# led_2835_rectangle_49point9X2point6cm.net
KiCad netlist of a schematic drawn in Altium Designer
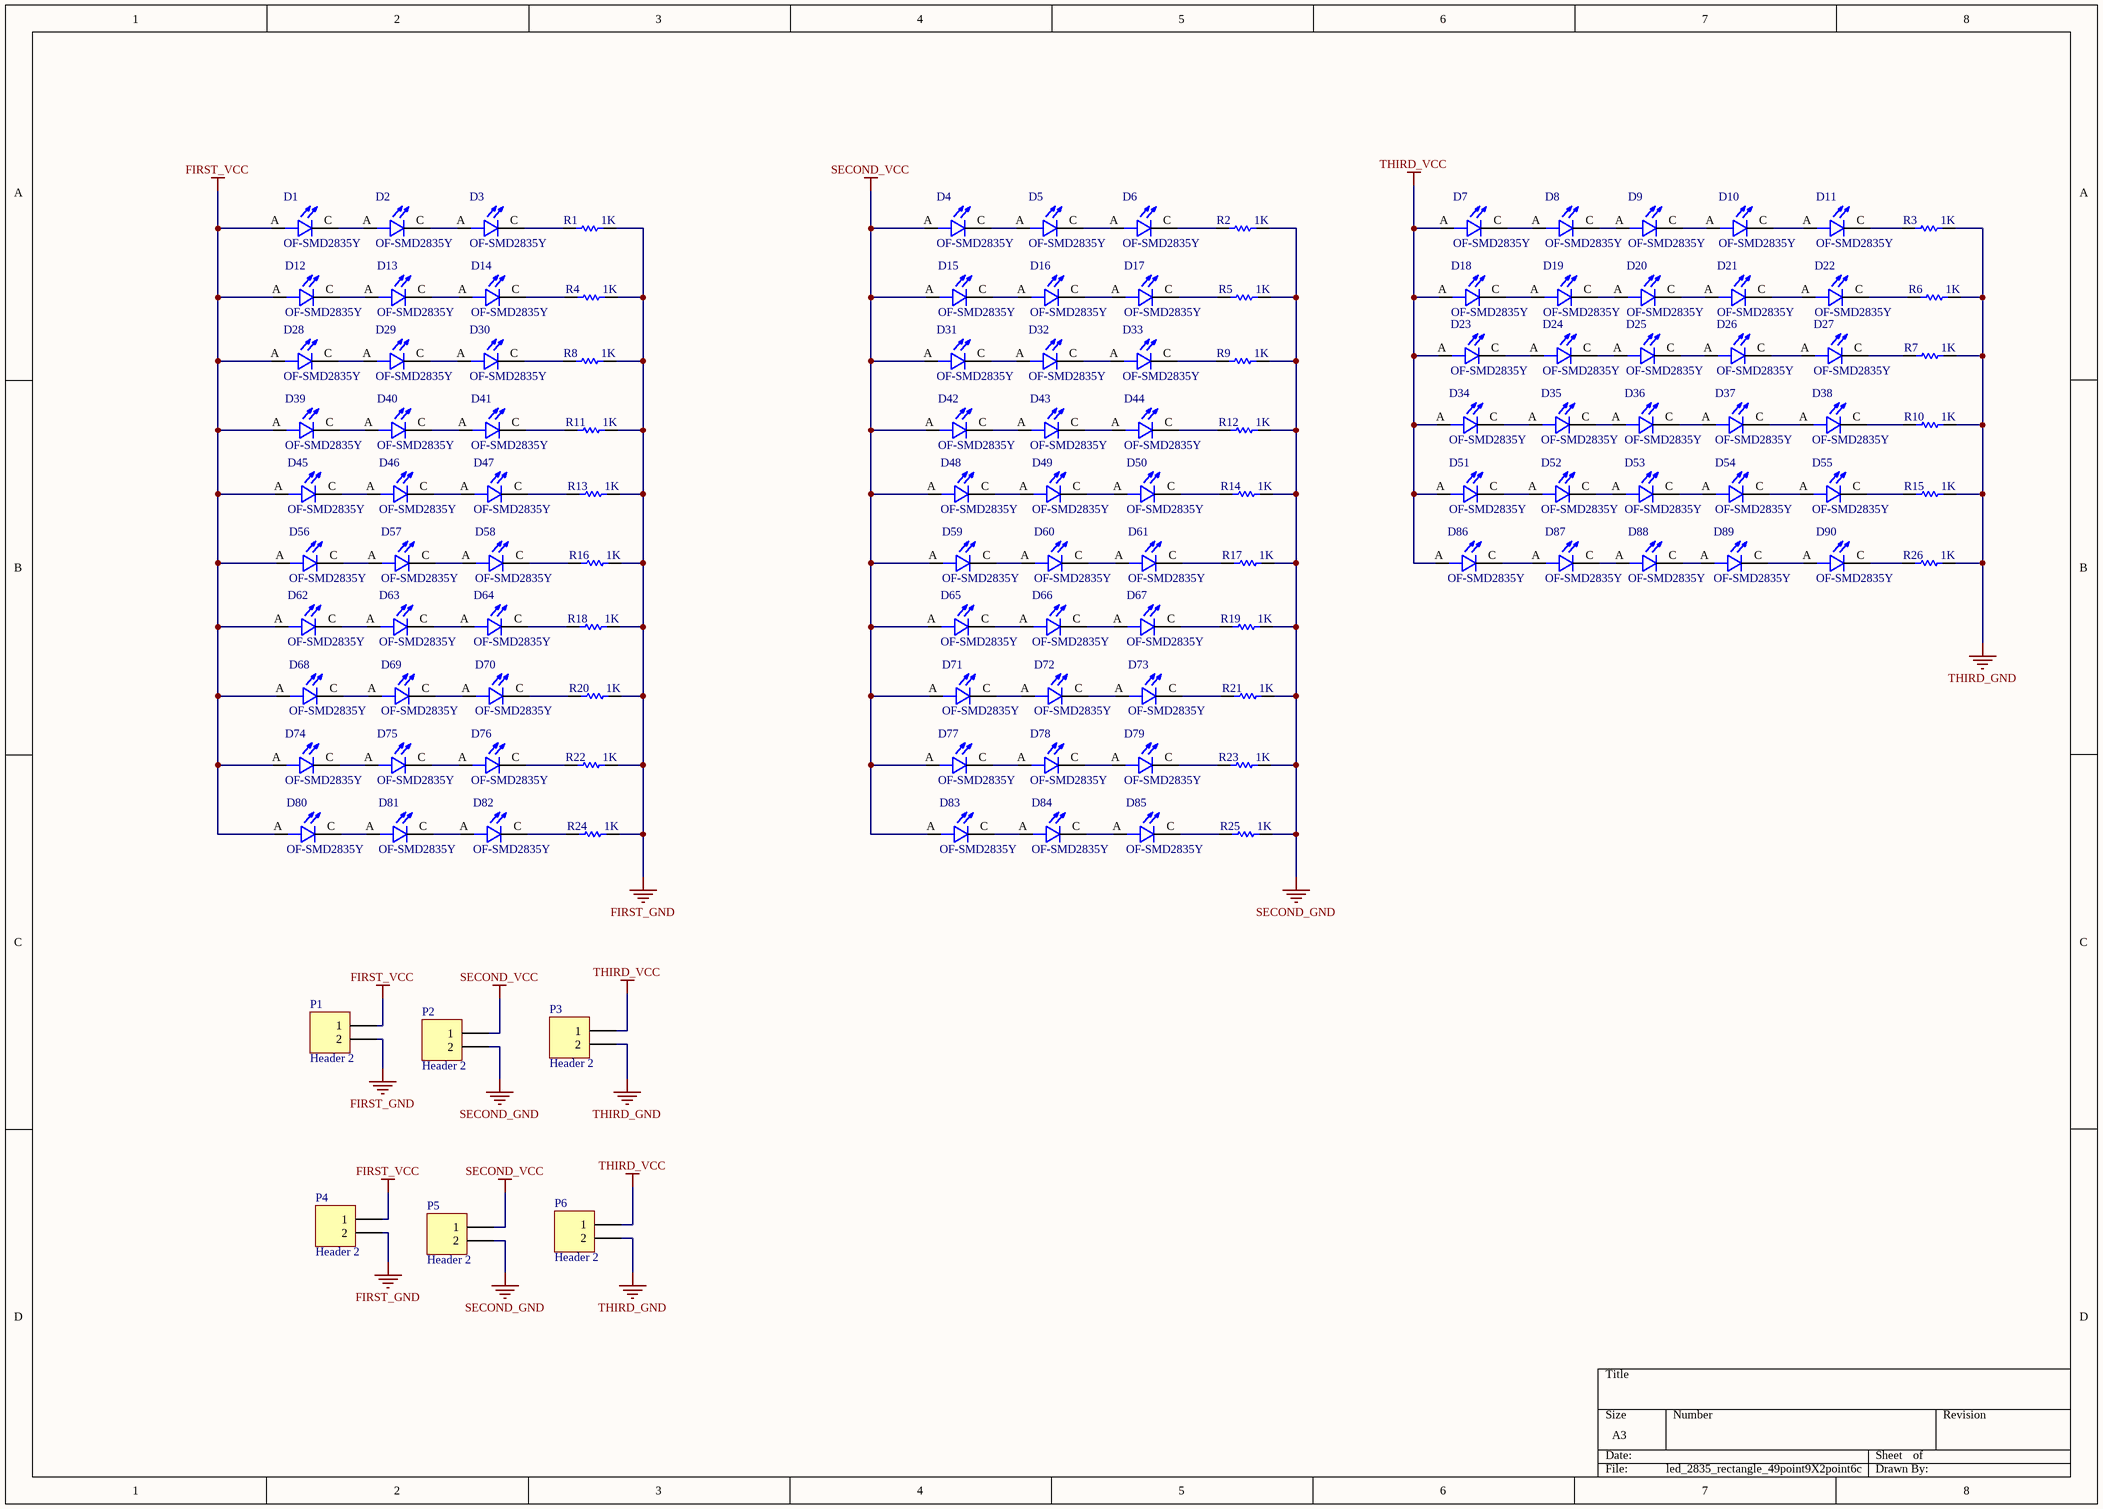
[diagram p0: led_2835_rectangle_49point9X2point6cm.SchDoc]

(export (version "E")
  (design (tool "Eeschema 10.0.6"))
  (components
    (comp (ref "D1")
      (value "OF-SMD2835Y")
      (footprint "LED_OF-SMD2835Y")
      (description "LED; SMD; 2835, PLCC2; yellow; 2200-2800mcd; 2.8x3.5x0.75mm; 120Â°")
      (libsource (lib "") (part "OF-SMD2835Y_4"))
    )
    (comp (ref "D2")
      (value "OF-SMD2835Y")
      (footprint "LED_OF-SMD2835Y")
      (description "LED; SMD; 2835, PLCC2; yellow; 2200-2800mcd; 2.8x3.5x0.75mm; 120Â°")
      (libsource (lib "") (part "OF-SMD2835Y_4"))
    )
    (comp (ref "D3")
      (value "OF-SMD2835Y")
      (footprint "LED_OF-SMD2835Y")
      (description "LED; SMD; 2835, PLCC2; yellow; 2200-2800mcd; 2.8x3.5x0.75mm; 120Â°")
      (libsource (lib "") (part "OF-SMD2835Y_4"))
    )
    (comp (ref "D4")
      (value "OF-SMD2835Y")
      (footprint "LED_OF-SMD2835Y")
      (description "LED; SMD; 2835, PLCC2; yellow; 2200-2800mcd; 2.8x3.5x0.75mm; 120Â°")
      (libsource (lib "") (part "OF-SMD2835Y_4"))
    )
    (comp (ref "D5")
      (value "OF-SMD2835Y")
      (footprint "LED_OF-SMD2835Y")
      (description "LED; SMD; 2835, PLCC2; yellow; 2200-2800mcd; 2.8x3.5x0.75mm; 120Â°")
      (libsource (lib "") (part "OF-SMD2835Y_4"))
    )
    (comp (ref "D6")
      (value "OF-SMD2835Y")
      (footprint "LED_OF-SMD2835Y")
      (description "LED; SMD; 2835, PLCC2; yellow; 2200-2800mcd; 2.8x3.5x0.75mm; 120Â°")
      (libsource (lib "") (part "OF-SMD2835Y_4"))
    )
    (comp (ref "D7")
      (value "OF-SMD2835Y")
      (footprint "LED_OF-SMD2835Y")
      (description "LED; SMD; 2835, PLCC2; yellow; 2200-2800mcd; 2.8x3.5x0.75mm; 120Â°")
      (libsource (lib "") (part "OF-SMD2835Y_3"))
    )
    (comp (ref "D8")
      (value "OF-SMD2835Y")
      (footprint "LED_OF-SMD2835Y")
      (description "LED; SMD; 2835, PLCC2; yellow; 2200-2800mcd; 2.8x3.5x0.75mm; 120Â°")
      (libsource (lib "") (part "OF-SMD2835Y_3"))
    )
    (comp (ref "D9")
      (value "OF-SMD2835Y")
      (footprint "LED_OF-SMD2835Y")
      (description "LED; SMD; 2835, PLCC2; yellow; 2200-2800mcd; 2.8x3.5x0.75mm; 120Â°")
      (libsource (lib "") (part "OF-SMD2835Y_3"))
    )
    (comp (ref "D10")
      (value "OF-SMD2835Y")
      (footprint "LED_OF-SMD2835Y")
      (description "LED; SMD; 2835, PLCC2; yellow; 2200-2800mcd; 2.8x3.5x0.75mm; 120Â°")
      (libsource (lib "") (part "OF-SMD2835Y_3"))
    )
    (comp (ref "D11")
      (value "OF-SMD2835Y")
      (footprint "LED_OF-SMD2835Y")
      (description "LED; SMD; 2835, PLCC2; yellow; 2200-2800mcd; 2.8x3.5x0.75mm; 120Â°")
      (libsource (lib "") (part "OF-SMD2835Y_3"))
    )
    (comp (ref "D12")
      (value "OF-SMD2835Y")
      (footprint "LED_OF-SMD2835Y")
      (description "LED; SMD; 2835, PLCC2; yellow; 2200-2800mcd; 2.8x3.5x0.75mm; 120Â°")
      (libsource (lib "") (part "OF-SMD2835Y_1"))
    )
    (comp (ref "D13")
      (value "OF-SMD2835Y")
      (footprint "LED_OF-SMD2835Y")
      (description "LED; SMD; 2835, PLCC2; yellow; 2200-2800mcd; 2.8x3.5x0.75mm; 120Â°")
      (libsource (lib "") (part "OF-SMD2835Y_1"))
    )
    (comp (ref "D14")
      (value "OF-SMD2835Y")
      (footprint "LED_OF-SMD2835Y")
      (description "LED; SMD; 2835, PLCC2; yellow; 2200-2800mcd; 2.8x3.5x0.75mm; 120Â°")
      (libsource (lib "") (part "OF-SMD2835Y_1"))
    )
    (comp (ref "D15")
      (value "OF-SMD2835Y")
      (footprint "LED_OF-SMD2835Y")
      (description "LED; SMD; 2835, PLCC2; yellow; 2200-2800mcd; 2.8x3.5x0.75mm; 120Â°")
      (libsource (lib "") (part "OF-SMD2835Y_3"))
    )
    (comp (ref "D16")
      (value "OF-SMD2835Y")
      (footprint "LED_OF-SMD2835Y")
      (description "LED; SMD; 2835, PLCC2; yellow; 2200-2800mcd; 2.8x3.5x0.75mm; 120Â°")
      (libsource (lib "") (part "OF-SMD2835Y_3"))
    )
    (comp (ref "D17")
      (value "OF-SMD2835Y")
      (footprint "LED_OF-SMD2835Y")
      (description "LED; SMD; 2835, PLCC2; yellow; 2200-2800mcd; 2.8x3.5x0.75mm; 120Â°")
      (libsource (lib "") (part "OF-SMD2835Y_3"))
    )
    (comp (ref "D18")
      (value "OF-SMD2835Y")
      (footprint "LED_OF-SMD2835Y")
      (description "LED; SMD; 2835, PLCC2; yellow; 2200-2800mcd; 2.8x3.5x0.75mm; 120Â°")
      (libsource (lib "") (part "OF-SMD2835Y_3"))
    )
    (comp (ref "D19")
      (value "OF-SMD2835Y")
      (footprint "LED_OF-SMD2835Y")
      (description "LED; SMD; 2835, PLCC2; yellow; 2200-2800mcd; 2.8x3.5x0.75mm; 120Â°")
      (libsource (lib "") (part "OF-SMD2835Y_3"))
    )
    (comp (ref "D20")
      (value "OF-SMD2835Y")
      (footprint "LED_OF-SMD2835Y")
      (description "LED; SMD; 2835, PLCC2; yellow; 2200-2800mcd; 2.8x3.5x0.75mm; 120Â°")
      (libsource (lib "") (part "OF-SMD2835Y_3"))
    )
    (comp (ref "D21")
      (value "OF-SMD2835Y")
      (footprint "LED_OF-SMD2835Y")
      (description "LED; SMD; 2835, PLCC2; yellow; 2200-2800mcd; 2.8x3.5x0.75mm; 120Â°")
      (libsource (lib "") (part "OF-SMD2835Y_3"))
    )
    (comp (ref "D22")
      (value "OF-SMD2835Y")
      (footprint "LED_OF-SMD2835Y")
      (description "LED; SMD; 2835, PLCC2; yellow; 2200-2800mcd; 2.8x3.5x0.75mm; 120Â°")
      (libsource (lib "") (part "OF-SMD2835Y_3"))
    )
    (comp (ref "D23")
      (value "OF-SMD2835Y")
      (footprint "LED_OF-SMD2835Y")
      (description "LED; SMD; 2835, PLCC2; yellow; 2200-2800mcd; 2.8x3.5x0.75mm; 120Â°")
      (libsource (lib "") (part "OF-SMD2835Y_3"))
    )
    (comp (ref "D24")
      (value "OF-SMD2835Y")
      (footprint "LED_OF-SMD2835Y")
      (description "LED; SMD; 2835, PLCC2; yellow; 2200-2800mcd; 2.8x3.5x0.75mm; 120Â°")
      (libsource (lib "") (part "OF-SMD2835Y_3"))
    )
    (comp (ref "D25")
      (value "OF-SMD2835Y")
      (footprint "LED_OF-SMD2835Y")
      (description "LED; SMD; 2835, PLCC2; yellow; 2200-2800mcd; 2.8x3.5x0.75mm; 120Â°")
      (libsource (lib "") (part "OF-SMD2835Y_3"))
    )
    (comp (ref "D26")
      (value "OF-SMD2835Y")
      (footprint "LED_OF-SMD2835Y")
      (description "LED; SMD; 2835, PLCC2; yellow; 2200-2800mcd; 2.8x3.5x0.75mm; 120Â°")
      (libsource (lib "") (part "OF-SMD2835Y_3"))
    )
    (comp (ref "D27")
      (value "OF-SMD2835Y")
      (footprint "LED_OF-SMD2835Y")
      (description "LED; SMD; 2835, PLCC2; yellow; 2200-2800mcd; 2.8x3.5x0.75mm; 120Â°")
      (libsource (lib "") (part "OF-SMD2835Y_3"))
    )
    (comp (ref "D28")
      (value "OF-SMD2835Y")
      (footprint "LED_OF-SMD2835Y")
      (description "LED; SMD; 2835, PLCC2; yellow; 2200-2800mcd; 2.8x3.5x0.75mm; 120Â°")
      (libsource (lib "") (part "OF-SMD2835Y_1"))
    )
    (comp (ref "D29")
      (value "OF-SMD2835Y")
      (footprint "LED_OF-SMD2835Y")
      (description "LED; SMD; 2835, PLCC2; yellow; 2200-2800mcd; 2.8x3.5x0.75mm; 120Â°")
      (libsource (lib "") (part "OF-SMD2835Y_1"))
    )
    (comp (ref "D30")
      (value "OF-SMD2835Y")
      (footprint "LED_OF-SMD2835Y")
      (description "LED; SMD; 2835, PLCC2; yellow; 2200-2800mcd; 2.8x3.5x0.75mm; 120Â°")
      (libsource (lib "") (part "OF-SMD2835Y_1"))
    )
    (comp (ref "D31")
      (value "OF-SMD2835Y")
      (footprint "LED_OF-SMD2835Y")
      (description "LED; SMD; 2835, PLCC2; yellow; 2200-2800mcd; 2.8x3.5x0.75mm; 120Â°")
      (libsource (lib "") (part "OF-SMD2835Y_3"))
    )
    (comp (ref "D32")
      (value "OF-SMD2835Y")
      (footprint "LED_OF-SMD2835Y")
      (description "LED; SMD; 2835, PLCC2; yellow; 2200-2800mcd; 2.8x3.5x0.75mm; 120Â°")
      (libsource (lib "") (part "OF-SMD2835Y_3"))
    )
    (comp (ref "D33")
      (value "OF-SMD2835Y")
      (footprint "LED_OF-SMD2835Y")
      (description "LED; SMD; 2835, PLCC2; yellow; 2200-2800mcd; 2.8x3.5x0.75mm; 120Â°")
      (libsource (lib "") (part "OF-SMD2835Y_3"))
    )
    (comp (ref "D34")
      (value "OF-SMD2835Y")
      (footprint "LED_OF-SMD2835Y")
      (description "LED; SMD; 2835, PLCC2; yellow; 2200-2800mcd; 2.8x3.5x0.75mm; 120Â°")
      (libsource (lib "") (part "OF-SMD2835Y_3"))
    )
    (comp (ref "D35")
      (value "OF-SMD2835Y")
      (footprint "LED_OF-SMD2835Y")
      (description "LED; SMD; 2835, PLCC2; yellow; 2200-2800mcd; 2.8x3.5x0.75mm; 120Â°")
      (libsource (lib "") (part "OF-SMD2835Y_3"))
    )
    (comp (ref "D36")
      (value "OF-SMD2835Y")
      (footprint "LED_OF-SMD2835Y")
      (description "LED; SMD; 2835, PLCC2; yellow; 2200-2800mcd; 2.8x3.5x0.75mm; 120Â°")
      (libsource (lib "") (part "OF-SMD2835Y_3"))
    )
    (comp (ref "D37")
      (value "OF-SMD2835Y")
      (footprint "LED_OF-SMD2835Y")
      (description "LED; SMD; 2835, PLCC2; yellow; 2200-2800mcd; 2.8x3.5x0.75mm; 120Â°")
      (libsource (lib "") (part "OF-SMD2835Y_3"))
    )
    (comp (ref "D38")
      (value "OF-SMD2835Y")
      (footprint "LED_OF-SMD2835Y")
      (description "LED; SMD; 2835, PLCC2; yellow; 2200-2800mcd; 2.8x3.5x0.75mm; 120Â°")
      (libsource (lib "") (part "OF-SMD2835Y_3"))
    )
    (comp (ref "D39")
      (value "OF-SMD2835Y")
      (footprint "LED_OF-SMD2835Y")
      (description "LED; SMD; 2835, PLCC2; yellow; 2200-2800mcd; 2.8x3.5x0.75mm; 120Â°")
      (libsource (lib "") (part "OF-SMD2835Y_1"))
    )
    (comp (ref "D40")
      (value "OF-SMD2835Y")
      (footprint "LED_OF-SMD2835Y")
      (description "LED; SMD; 2835, PLCC2; yellow; 2200-2800mcd; 2.8x3.5x0.75mm; 120Â°")
      (libsource (lib "") (part "OF-SMD2835Y_1"))
    )
    (comp (ref "D41")
      (value "OF-SMD2835Y")
      (footprint "LED_OF-SMD2835Y")
      (description "LED; SMD; 2835, PLCC2; yellow; 2200-2800mcd; 2.8x3.5x0.75mm; 120Â°")
      (libsource (lib "") (part "OF-SMD2835Y_1"))
    )
    (comp (ref "D42")
      (value "OF-SMD2835Y")
      (footprint "LED_OF-SMD2835Y")
      (description "LED; SMD; 2835, PLCC2; yellow; 2200-2800mcd; 2.8x3.5x0.75mm; 120Â°")
      (libsource (lib "") (part "OF-SMD2835Y_3"))
    )
    (comp (ref "D43")
      (value "OF-SMD2835Y")
      (footprint "LED_OF-SMD2835Y")
      (description "LED; SMD; 2835, PLCC2; yellow; 2200-2800mcd; 2.8x3.5x0.75mm; 120Â°")
      (libsource (lib "") (part "OF-SMD2835Y_3"))
    )
    (comp (ref "D44")
      (value "OF-SMD2835Y")
      (footprint "LED_OF-SMD2835Y")
      (description "LED; SMD; 2835, PLCC2; yellow; 2200-2800mcd; 2.8x3.5x0.75mm; 120Â°")
      (libsource (lib "") (part "OF-SMD2835Y_3"))
    )
    (comp (ref "D45")
      (value "OF-SMD2835Y")
      (footprint "LED_OF-SMD2835Y")
      (description "LED; SMD; 2835, PLCC2; yellow; 2200-2800mcd; 2.8x3.5x0.75mm; 120Â°")
      (libsource (lib "") (part "OF-SMD2835Y_2"))
    )
    (comp (ref "D46")
      (value "OF-SMD2835Y")
      (footprint "LED_OF-SMD2835Y")
      (description "LED; SMD; 2835, PLCC2; yellow; 2200-2800mcd; 2.8x3.5x0.75mm; 120Â°")
      (libsource (lib "") (part "OF-SMD2835Y_2"))
    )
    (comp (ref "D47")
      (value "OF-SMD2835Y")
      (footprint "LED_OF-SMD2835Y")
      (description "LED; SMD; 2835, PLCC2; yellow; 2200-2800mcd; 2.8x3.5x0.75mm; 120Â°")
      (libsource (lib "") (part "OF-SMD2835Y_2"))
    )
    (comp (ref "D48")
      (value "OF-SMD2835Y")
      (footprint "LED_OF-SMD2835Y")
      (description "LED; SMD; 2835, PLCC2; yellow; 2200-2800mcd; 2.8x3.5x0.75mm; 120Â°")
      (libsource (lib "") (part "OF-SMD2835Y_2"))
    )
    (comp (ref "D49")
      (value "OF-SMD2835Y")
      (footprint "LED_OF-SMD2835Y")
      (description "LED; SMD; 2835, PLCC2; yellow; 2200-2800mcd; 2.8x3.5x0.75mm; 120Â°")
      (libsource (lib "") (part "OF-SMD2835Y_2"))
    )
    (comp (ref "D50")
      (value "OF-SMD2835Y")
      (footprint "LED_OF-SMD2835Y")
      (description "LED; SMD; 2835, PLCC2; yellow; 2200-2800mcd; 2.8x3.5x0.75mm; 120Â°")
      (libsource (lib "") (part "OF-SMD2835Y_2"))
    )
    (comp (ref "D51")
      (value "OF-SMD2835Y")
      (footprint "LED_OF-SMD2835Y")
      (description "LED; SMD; 2835, PLCC2; yellow; 2200-2800mcd; 2.8x3.5x0.75mm; 120Â°")
      (libsource (lib "") (part "OF-SMD2835Y_3"))
    )
    (comp (ref "D52")
      (value "OF-SMD2835Y")
      (footprint "LED_OF-SMD2835Y")
      (description "LED; SMD; 2835, PLCC2; yellow; 2200-2800mcd; 2.8x3.5x0.75mm; 120Â°")
      (libsource (lib "") (part "OF-SMD2835Y_3"))
    )
    (comp (ref "D53")
      (value "OF-SMD2835Y")
      (footprint "LED_OF-SMD2835Y")
      (description "LED; SMD; 2835, PLCC2; yellow; 2200-2800mcd; 2.8x3.5x0.75mm; 120Â°")
      (libsource (lib "") (part "OF-SMD2835Y_3"))
    )
    (comp (ref "D54")
      (value "OF-SMD2835Y")
      (footprint "LED_OF-SMD2835Y")
      (description "LED; SMD; 2835, PLCC2; yellow; 2200-2800mcd; 2.8x3.5x0.75mm; 120Â°")
      (libsource (lib "") (part "OF-SMD2835Y_3"))
    )
    (comp (ref "D55")
      (value "OF-SMD2835Y")
      (footprint "LED_OF-SMD2835Y")
      (description "LED; SMD; 2835, PLCC2; yellow; 2200-2800mcd; 2.8x3.5x0.75mm; 120Â°")
      (libsource (lib "") (part "OF-SMD2835Y_3"))
    )
    (comp (ref "D56")
      (value "OF-SMD2835Y")
      (footprint "LED_OF-SMD2835Y")
      (description "LED; SMD; 2835, PLCC2; yellow; 2200-2800mcd; 2.8x3.5x0.75mm; 120Â°")
      (libsource (lib "") (part "OF-SMD2835Y_4"))
    )
    (comp (ref "D57")
      (value "OF-SMD2835Y")
      (footprint "LED_OF-SMD2835Y")
      (description "LED; SMD; 2835, PLCC2; yellow; 2200-2800mcd; 2.8x3.5x0.75mm; 120Â°")
      (libsource (lib "") (part "OF-SMD2835Y_4"))
    )
    (comp (ref "D58")
      (value "OF-SMD2835Y")
      (footprint "LED_OF-SMD2835Y")
      (description "LED; SMD; 2835, PLCC2; yellow; 2200-2800mcd; 2.8x3.5x0.75mm; 120Â°")
      (libsource (lib "") (part "OF-SMD2835Y_4"))
    )
    (comp (ref "D59")
      (value "OF-SMD2835Y")
      (footprint "LED_OF-SMD2835Y")
      (description "LED; SMD; 2835, PLCC2; yellow; 2200-2800mcd; 2.8x3.5x0.75mm; 120Â°")
      (libsource (lib "OF-SMD2835Y") (part "OF-SMD2835Y"))
    )
    (comp (ref "D60")
      (value "OF-SMD2835Y")
      (footprint "LED_OF-SMD2835Y")
      (description "LED; SMD; 2835, PLCC2; yellow; 2200-2800mcd; 2.8x3.5x0.75mm; 120Â°")
      (libsource (lib "OF-SMD2835Y") (part "OF-SMD2835Y"))
    )
    (comp (ref "D61")
      (value "OF-SMD2835Y")
      (footprint "LED_OF-SMD2835Y")
      (description "LED; SMD; 2835, PLCC2; yellow; 2200-2800mcd; 2.8x3.5x0.75mm; 120Â°")
      (libsource (lib "OF-SMD2835Y") (part "OF-SMD2835Y"))
    )
    (comp (ref "D62")
      (value "OF-SMD2835Y")
      (footprint "LED_OF-SMD2835Y")
      (description "LED; SMD; 2835, PLCC2; yellow; 2200-2800mcd; 2.8x3.5x0.75mm; 120Â°")
      (libsource (lib "") (part "OF-SMD2835Y_4"))
    )
    (comp (ref "D63")
      (value "OF-SMD2835Y")
      (footprint "LED_OF-SMD2835Y")
      (description "LED; SMD; 2835, PLCC2; yellow; 2200-2800mcd; 2.8x3.5x0.75mm; 120Â°")
      (libsource (lib "") (part "OF-SMD2835Y_4"))
    )
    (comp (ref "D64")
      (value "OF-SMD2835Y")
      (footprint "LED_OF-SMD2835Y")
      (description "LED; SMD; 2835, PLCC2; yellow; 2200-2800mcd; 2.8x3.5x0.75mm; 120Â°")
      (libsource (lib "") (part "OF-SMD2835Y_4"))
    )
    (comp (ref "D65")
      (value "OF-SMD2835Y")
      (footprint "LED_OF-SMD2835Y")
      (description "LED; SMD; 2835, PLCC2; yellow; 2200-2800mcd; 2.8x3.5x0.75mm; 120Â°")
      (libsource (lib "OF-SMD2835Y") (part "OF-SMD2835Y"))
    )
    (comp (ref "D66")
      (value "OF-SMD2835Y")
      (footprint "LED_OF-SMD2835Y")
      (description "LED; SMD; 2835, PLCC2; yellow; 2200-2800mcd; 2.8x3.5x0.75mm; 120Â°")
      (libsource (lib "OF-SMD2835Y") (part "OF-SMD2835Y"))
    )
    (comp (ref "D67")
      (value "OF-SMD2835Y")
      (footprint "LED_OF-SMD2835Y")
      (description "LED; SMD; 2835, PLCC2; yellow; 2200-2800mcd; 2.8x3.5x0.75mm; 120Â°")
      (libsource (lib "OF-SMD2835Y") (part "OF-SMD2835Y"))
    )
    (comp (ref "D68")
      (value "OF-SMD2835Y")
      (footprint "LED_OF-SMD2835Y")
      (description "LED; SMD; 2835, PLCC2; yellow; 2200-2800mcd; 2.8x3.5x0.75mm; 120Â°")
      (libsource (lib "") (part "OF-SMD2835Y_4"))
    )
    (comp (ref "D69")
      (value "OF-SMD2835Y")
      (footprint "LED_OF-SMD2835Y")
      (description "LED; SMD; 2835, PLCC2; yellow; 2200-2800mcd; 2.8x3.5x0.75mm; 120Â°")
      (libsource (lib "") (part "OF-SMD2835Y_4"))
    )
    (comp (ref "D70")
      (value "OF-SMD2835Y")
      (footprint "LED_OF-SMD2835Y")
      (description "LED; SMD; 2835, PLCC2; yellow; 2200-2800mcd; 2.8x3.5x0.75mm; 120Â°")
      (libsource (lib "") (part "OF-SMD2835Y_4"))
    )
    (comp (ref "D71")
      (value "OF-SMD2835Y")
      (footprint "LED_OF-SMD2835Y")
      (description "LED; SMD; 2835, PLCC2; yellow; 2200-2800mcd; 2.8x3.5x0.75mm; 120Â°")
      (libsource (lib "OF-SMD2835Y") (part "OF-SMD2835Y"))
    )
    (comp (ref "D72")
      (value "OF-SMD2835Y")
      (footprint "LED_OF-SMD2835Y")
      (description "LED; SMD; 2835, PLCC2; yellow; 2200-2800mcd; 2.8x3.5x0.75mm; 120Â°")
      (libsource (lib "OF-SMD2835Y") (part "OF-SMD2835Y"))
    )
    (comp (ref "D73")
      (value "OF-SMD2835Y")
      (footprint "LED_OF-SMD2835Y")
      (description "LED; SMD; 2835, PLCC2; yellow; 2200-2800mcd; 2.8x3.5x0.75mm; 120Â°")
      (libsource (lib "OF-SMD2835Y") (part "OF-SMD2835Y"))
    )
    (comp (ref "D74")
      (value "OF-SMD2835Y")
      (footprint "LED_OF-SMD2835Y")
      (description "LED; SMD; 2835, PLCC2; yellow; 2200-2800mcd; 2.8x3.5x0.75mm; 120Â°")
      (libsource (lib "") (part "OF-SMD2835Y_4"))
    )
    (comp (ref "D75")
      (value "OF-SMD2835Y")
      (footprint "LED_OF-SMD2835Y")
      (description "LED; SMD; 2835, PLCC2; yellow; 2200-2800mcd; 2.8x3.5x0.75mm; 120Â°")
      (libsource (lib "") (part "OF-SMD2835Y_4"))
    )
    (comp (ref "D76")
      (value "OF-SMD2835Y")
      (footprint "LED_OF-SMD2835Y")
      (description "LED; SMD; 2835, PLCC2; yellow; 2200-2800mcd; 2.8x3.5x0.75mm; 120Â°")
      (libsource (lib "") (part "OF-SMD2835Y_4"))
    )
    (comp (ref "D77")
      (value "OF-SMD2835Y")
      (footprint "LED_OF-SMD2835Y")
      (description "LED; SMD; 2835, PLCC2; yellow; 2200-2800mcd; 2.8x3.5x0.75mm; 120Â°")
      (libsource (lib "OF-SMD2835Y") (part "OF-SMD2835Y"))
    )
    (comp (ref "D78")
      (value "OF-SMD2835Y")
      (footprint "LED_OF-SMD2835Y")
      (description "LED; SMD; 2835, PLCC2; yellow; 2200-2800mcd; 2.8x3.5x0.75mm; 120Â°")
      (libsource (lib "OF-SMD2835Y") (part "OF-SMD2835Y"))
    )
    (comp (ref "D79")
      (value "OF-SMD2835Y")
      (footprint "LED_OF-SMD2835Y")
      (description "LED; SMD; 2835, PLCC2; yellow; 2200-2800mcd; 2.8x3.5x0.75mm; 120Â°")
      (libsource (lib "OF-SMD2835Y") (part "OF-SMD2835Y"))
    )
    (comp (ref "D80")
      (value "OF-SMD2835Y")
      (footprint "LED_OF-SMD2835Y")
      (description "LED; SMD; 2835, PLCC2; yellow; 2200-2800mcd; 2.8x3.5x0.75mm; 120Â°")
      (libsource (lib "") (part "OF-SMD2835Y_1"))
    )
    (comp (ref "D81")
      (value "OF-SMD2835Y")
      (footprint "LED_OF-SMD2835Y")
      (description "LED; SMD; 2835, PLCC2; yellow; 2200-2800mcd; 2.8x3.5x0.75mm; 120Â°")
      (libsource (lib "") (part "OF-SMD2835Y_1"))
    )
    (comp (ref "D82")
      (value "OF-SMD2835Y")
      (footprint "LED_OF-SMD2835Y")
      (description "LED; SMD; 2835, PLCC2; yellow; 2200-2800mcd; 2.8x3.5x0.75mm; 120Â°")
      (libsource (lib "") (part "OF-SMD2835Y_1"))
    )
    (comp (ref "D83")
      (value "OF-SMD2835Y")
      (footprint "LED_OF-SMD2835Y")
      (description "LED; SMD; 2835, PLCC2; yellow; 2200-2800mcd; 2.8x3.5x0.75mm; 120Â°")
      (libsource (lib "") (part "OF-SMD2835Y_3"))
    )
    (comp (ref "D84")
      (value "OF-SMD2835Y")
      (footprint "LED_OF-SMD2835Y")
      (description "LED; SMD; 2835, PLCC2; yellow; 2200-2800mcd; 2.8x3.5x0.75mm; 120Â°")
      (libsource (lib "") (part "OF-SMD2835Y_3"))
    )
    (comp (ref "D85")
      (value "OF-SMD2835Y")
      (footprint "LED_OF-SMD2835Y")
      (description "LED; SMD; 2835, PLCC2; yellow; 2200-2800mcd; 2.8x3.5x0.75mm; 120Â°")
      (libsource (lib "") (part "OF-SMD2835Y_3"))
    )
    (comp (ref "D86")
      (value "OF-SMD2835Y")
      (footprint "LED_OF-SMD2835Y")
      (description "LED; SMD; 2835, PLCC2; yellow; 2200-2800mcd; 2.8x3.5x0.75mm; 120Â°")
      (libsource (lib "OF-SMD2835Y") (part "OF-SMD2835Y"))
    )
    (comp (ref "D87")
      (value "OF-SMD2835Y")
      (footprint "LED_OF-SMD2835Y")
      (description "LED; SMD; 2835, PLCC2; yellow; 2200-2800mcd; 2.8x3.5x0.75mm; 120Â°")
      (libsource (lib "OF-SMD2835Y") (part "OF-SMD2835Y"))
    )
    (comp (ref "D88")
      (value "OF-SMD2835Y")
      (footprint "LED_OF-SMD2835Y")
      (description "LED; SMD; 2835, PLCC2; yellow; 2200-2800mcd; 2.8x3.5x0.75mm; 120Â°")
      (libsource (lib "OF-SMD2835Y") (part "OF-SMD2835Y"))
    )
    (comp (ref "D89")
      (value "OF-SMD2835Y")
      (footprint "LED_OF-SMD2835Y")
      (description "LED; SMD; 2835, PLCC2; yellow; 2200-2800mcd; 2.8x3.5x0.75mm; 120Â°")
      (libsource (lib "OF-SMD2835Y") (part "OF-SMD2835Y"))
    )
    (comp (ref "D90")
      (value "OF-SMD2835Y")
      (footprint "LED_OF-SMD2835Y")
      (description "LED; SMD; 2835, PLCC2; yellow; 2200-2800mcd; 2.8x3.5x0.75mm; 120Â°")
      (libsource (lib "OF-SMD2835Y") (part "OF-SMD2835Y"))
    )
    (comp (ref "P1")
      (value "Header 2")
      (footprint "HDR1X2_SMD")
      (description "Header, 2-Pin")
      (fields (field (name "PUBLISHER") "Altium Limited"))
      (libsource (lib "Miscellaneous Connectors") (part "Header 2"))
    )
    (comp (ref "P2")
      (value "Header 2")
      (footprint "HDR1X2_SMD")
      (description "Header, 2-Pin")
      (fields (field (name "PUBLISHER") "Altium Limited"))
      (libsource (lib "Miscellaneous Connectors") (part "Header 2"))
    )
    (comp (ref "P3")
      (value "Header 2")
      (footprint "HDR1X2_SMD")
      (description "Header, 2-Pin")
      (fields (field (name "PUBLISHER") "Altium Limited"))
      (libsource (lib "Miscellaneous Connectors") (part "Header 2"))
    )
    (comp (ref "P4")
      (value "Header 2")
      (footprint "HDR1X2_SMD")
      (description "Header, 2-Pin")
      (fields (field (name "PUBLISHER") "Altium Limited"))
      (libsource (lib "Miscellaneous Connectors") (part "Header 2"))
    )
    (comp (ref "P5")
      (value "Header 2")
      (footprint "HDR1X2_SMD")
      (description "Header, 2-Pin")
      (fields (field (name "PUBLISHER") "Altium Limited"))
      (libsource (lib "Miscellaneous Connectors") (part "Header 2"))
    )
    (comp (ref "P6")
      (value "Header 2")
      (footprint "HDR1X2_SMD")
      (description "Header, 2-Pin")
      (fields (field (name "PUBLISHER") "Altium Limited"))
      (libsource (lib "Miscellaneous Connectors") (part "Header 2"))
    )
    (comp (ref "R1")
      (value "1K")
      (footprint "R2512")
      (description "Resistor")
      (fields (field (name "PUBLISHER") "Altium Limited"))
      (libsource (lib "Miscellaneous Devices") (part "Res1"))
    )
    (comp (ref "R2")
      (value "1K")
      (footprint "R2512")
      (description "Resistor")
      (fields (field (name "PUBLISHER") "Altium Limited"))
      (libsource (lib "Miscellaneous Devices") (part "Res1"))
    )
    (comp (ref "R3")
      (value "1K")
      (footprint "R2512")
      (description "Resistor")
      (fields (field (name "PUBLISHER") "Altium Limited"))
      (libsource (lib "Miscellaneous Devices") (part "Res1"))
    )
    (comp (ref "R4")
      (value "1K")
      (footprint "R2512")
      (description "Resistor")
      (fields (field (name "PUBLISHER") "Altium Limited"))
      (libsource (lib "Miscellaneous Devices") (part "Res1"))
    )
    (comp (ref "R5")
      (value "1K")
      (footprint "R2512")
      (description "Resistor")
      (fields (field (name "PUBLISHER") "Altium Limited"))
      (libsource (lib "Miscellaneous Devices") (part "Res1"))
    )
    (comp (ref "R6")
      (value "1K")
      (footprint "R2512")
      (description "Resistor")
      (fields (field (name "PUBLISHER") "Altium Limited"))
      (libsource (lib "Miscellaneous Devices") (part "Res1"))
    )
    (comp (ref "R7")
      (value "1K")
      (footprint "R2512")
      (description "Resistor")
      (fields (field (name "PUBLISHER") "Altium Limited"))
      (libsource (lib "Miscellaneous Devices") (part "Res1"))
    )
    (comp (ref "R8")
      (value "1K")
      (footprint "R2512")
      (description "Resistor")
      (fields (field (name "PUBLISHER") "Altium Limited"))
      (libsource (lib "Miscellaneous Devices") (part "Res1"))
    )
    (comp (ref "R9")
      (value "1K")
      (footprint "R2512")
      (description "Resistor")
      (fields (field (name "PUBLISHER") "Altium Limited"))
      (libsource (lib "Miscellaneous Devices") (part "Res1"))
    )
    (comp (ref "R10")
      (value "1K")
      (footprint "R2512")
      (description "Resistor")
      (fields (field (name "PUBLISHER") "Altium Limited"))
      (libsource (lib "Miscellaneous Devices") (part "Res1"))
    )
    (comp (ref "R11")
      (value "1K")
      (footprint "R2512")
      (description "Resistor")
      (fields (field (name "PUBLISHER") "Altium Limited"))
      (libsource (lib "Miscellaneous Devices") (part "Res1"))
    )
    (comp (ref "R12")
      (value "1K")
      (footprint "R2512")
      (description "Resistor")
      (fields (field (name "PUBLISHER") "Altium Limited"))
      (libsource (lib "Miscellaneous Devices") (part "Res1"))
    )
    (comp (ref "R13")
      (value "1K")
      (footprint "R2512")
      (description "Resistor")
      (fields (field (name "PUBLISHER") "Altium Limited"))
      (libsource (lib "Miscellaneous Devices") (part "Res1"))
    )
    (comp (ref "R14")
      (value "1K")
      (footprint "R2512")
      (description "Resistor")
      (fields (field (name "PUBLISHER") "Altium Limited"))
      (libsource (lib "Miscellaneous Devices") (part "Res1"))
    )
    (comp (ref "R15")
      (value "1K")
      (footprint "R2512")
      (description "Resistor")
      (fields (field (name "PUBLISHER") "Altium Limited"))
      (libsource (lib "Miscellaneous Devices") (part "Res1"))
    )
    (comp (ref "R16")
      (value "1K")
      (footprint "R2512")
      (description "Resistor")
      (fields (field (name "PUBLISHER") "Altium Limited"))
      (libsource (lib "Miscellaneous Devices") (part "Res1"))
    )
    (comp (ref "R17")
      (value "1K")
      (footprint "R2512")
      (description "Resistor")
      (fields (field (name "PUBLISHER") "Altium Limited"))
      (libsource (lib "Miscellaneous Devices") (part "Res1"))
    )
    (comp (ref "R18")
      (value "1K")
      (footprint "R2512")
      (description "Resistor")
      (fields (field (name "PUBLISHER") "Altium Limited"))
      (libsource (lib "Miscellaneous Devices") (part "Res1"))
    )
    (comp (ref "R19")
      (value "1K")
      (footprint "R2512")
      (description "Resistor")
      (fields (field (name "PUBLISHER") "Altium Limited"))
      (libsource (lib "Miscellaneous Devices") (part "Res1"))
    )
    (comp (ref "R20")
      (value "1K")
      (footprint "R2512")
      (description "Resistor")
      (fields (field (name "PUBLISHER") "Altium Limited"))
      (libsource (lib "Miscellaneous Devices") (part "Res1"))
    )
    (comp (ref "R21")
      (value "1K")
      (footprint "R2512")
      (description "Resistor")
      (fields (field (name "PUBLISHER") "Altium Limited"))
      (libsource (lib "Miscellaneous Devices") (part "Res1"))
    )
    (comp (ref "R22")
      (value "1K")
      (footprint "R2512")
      (description "Resistor")
      (fields (field (name "PUBLISHER") "Altium Limited"))
      (libsource (lib "Miscellaneous Devices") (part "Res1"))
    )
    (comp (ref "R23")
      (value "1K")
      (footprint "R2512")
      (description "Resistor")
      (fields (field (name "PUBLISHER") "Altium Limited"))
      (libsource (lib "Miscellaneous Devices") (part "Res1"))
    )
    (comp (ref "R24")
      (value "1K")
      (footprint "R2512")
      (description "Resistor")
      (fields (field (name "PUBLISHER") "Altium Limited"))
      (libsource (lib "Miscellaneous Devices") (part "Res1"))
    )
    (comp (ref "R25")
      (value "1K")
      (footprint "R2512")
      (description "Resistor")
      (fields (field (name "PUBLISHER") "Altium Limited"))
      (libsource (lib "Miscellaneous Devices") (part "Res1"))
    )
    (comp (ref "R26")
      (value "1K")
      (footprint "R2512")
      (description "Resistor")
      (fields (field (name "PUBLISHER") "Altium Limited"))
      (libsource (lib "Miscellaneous Devices") (part "Res1"))
    )
  )
  (nets
    (net (code "1") (name "FIRST_GND") (class "Default")
      (node (ref "P1") (pin "GND") (pinfunction "2_GND") (pintype "passive"))
      (node (ref "P4") (pin "GND") (pinfunction "2_GND") (pintype "passive"))
      (node (ref "R1") (pin "2") (pinfunction "2_2") (pintype "passive"))
      (node (ref "R11") (pin "2") (pinfunction "2_2") (pintype "passive"))
      (node (ref "R13") (pin "2") (pinfunction "2_2") (pintype "passive"))
      (node (ref "R16") (pin "2") (pinfunction "2_2") (pintype "passive"))
      (node (ref "R18") (pin "2") (pinfunction "2_2") (pintype "passive"))
      (node (ref "R20") (pin "2") (pinfunction "2_2") (pintype "passive"))
      (node (ref "R22") (pin "2") (pinfunction "2_2") (pintype "passive"))
      (node (ref "R24") (pin "2") (pinfunction "2_2") (pintype "passive"))
      (node (ref "R4") (pin "2") (pinfunction "2_2") (pintype "passive"))
      (node (ref "R8") (pin "2") (pinfunction "2_2") (pintype "passive"))
    )
    (net (code "2") (name "FIRST_VCC") (class "Default")
      (node (ref "D1") (pin "A") (pinfunction "A_A") (pintype "passive"))
      (node (ref "D12") (pin "A") (pinfunction "A_A") (pintype "passive"))
      (node (ref "D28") (pin "A") (pinfunction "A_A") (pintype "passive"))
      (node (ref "D39") (pin "A") (pinfunction "A_A") (pintype "passive"))
      (node (ref "D45") (pin "A") (pinfunction "A_A") (pintype "passive"))
      (node (ref "D56") (pin "A") (pinfunction "A_A") (pintype "passive"))
      (node (ref "D62") (pin "A") (pinfunction "A_A") (pintype "passive"))
      (node (ref "D68") (pin "A") (pinfunction "A_A") (pintype "passive"))
      (node (ref "D74") (pin "A") (pinfunction "A_A") (pintype "passive"))
      (node (ref "D80") (pin "A") (pinfunction "A_A") (pintype "passive"))
      (node (ref "P1") (pin "VCC") (pinfunction "1_VCC") (pintype "passive"))
      (node (ref "P4") (pin "VCC") (pinfunction "1_VCC") (pintype "passive"))
    )
    (net (code "3") (name "Net-(D1-PadC)") (class "Default")
      (node (ref "D1") (pin "C") (pinfunction "C_C") (pintype "passive"))
      (node (ref "D2") (pin "A") (pinfunction "A_A") (pintype "passive"))
    )
    (net (code "4") (name "Net-(D2-PadC)") (class "Default")
      (node (ref "D2") (pin "C") (pinfunction "C_C") (pintype "passive"))
      (node (ref "D3") (pin "A") (pinfunction "A_A") (pintype "passive"))
    )
    (net (code "5") (name "Net-(D3-PadC)") (class "Default")
      (node (ref "D3") (pin "C") (pinfunction "C_C") (pintype "passive"))
      (node (ref "R1") (pin "1") (pinfunction "1_1") (pintype "passive"))
    )
    (net (code "6") (name "Net-(D4-PadC)") (class "Default")
      (node (ref "D4") (pin "C") (pinfunction "C_C") (pintype "passive"))
      (node (ref "D5") (pin "A") (pinfunction "A_A") (pintype "passive"))
    )
    (net (code "7") (name "Net-(D5-PadC)") (class "Default")
      (node (ref "D5") (pin "C") (pinfunction "C_C") (pintype "passive"))
      (node (ref "D6") (pin "A") (pinfunction "A_A") (pintype "passive"))
    )
    (net (code "8") (name "Net-(D6-PadC)") (class "Default")
      (node (ref "D6") (pin "C") (pinfunction "C_C") (pintype "passive"))
      (node (ref "R2") (pin "1") (pinfunction "1_1") (pintype "passive"))
    )
    (net (code "9") (name "Net-(D7-PadC)") (class "Default")
      (node (ref "D7") (pin "C") (pinfunction "C_C") (pintype "passive"))
      (node (ref "D8") (pin "A") (pinfunction "A_A") (pintype "passive"))
    )
    (net (code "10") (name "Net-(D8-PadC)") (class "Default")
      (node (ref "D8") (pin "C") (pinfunction "C_C") (pintype "passive"))
      (node (ref "D9") (pin "A") (pinfunction "A_A") (pintype "passive"))
    )
    (net (code "11") (name "Net-(D10-PadA)") (class "Default")
      (node (ref "D10") (pin "A") (pinfunction "A_A") (pintype "passive"))
      (node (ref "D9") (pin "C") (pinfunction "C_C") (pintype "passive"))
    )
    (net (code "12") (name "Net-(D10-PadC)") (class "Default")
      (node (ref "D10") (pin "C") (pinfunction "C_C") (pintype "passive"))
      (node (ref "D11") (pin "A") (pinfunction "A_A") (pintype "passive"))
    )
    (net (code "13") (name "Net-(D11-PadC)") (class "Default")
      (node (ref "D11") (pin "C") (pinfunction "C_C") (pintype "passive"))
      (node (ref "R3") (pin "1") (pinfunction "1_1") (pintype "passive"))
    )
    (net (code "14") (name "Net-(D12-PadC)") (class "Default")
      (node (ref "D12") (pin "C") (pinfunction "C_C") (pintype "passive"))
      (node (ref "D13") (pin "A") (pinfunction "A_A") (pintype "passive"))
    )
    (net (code "15") (name "Net-(D13-PadC)") (class "Default")
      (node (ref "D13") (pin "C") (pinfunction "C_C") (pintype "passive"))
      (node (ref "D14") (pin "A") (pinfunction "A_A") (pintype "passive"))
    )
    (net (code "16") (name "Net-(D14-PadC)") (class "Default")
      (node (ref "D14") (pin "C") (pinfunction "C_C") (pintype "passive"))
      (node (ref "R4") (pin "1") (pinfunction "1_1") (pintype "passive"))
    )
    (net (code "17") (name "Net-(D15-PadC)") (class "Default")
      (node (ref "D15") (pin "C") (pinfunction "C_C") (pintype "passive"))
      (node (ref "D16") (pin "A") (pinfunction "A_A") (pintype "passive"))
    )
    (net (code "18") (name "Net-(D16-PadC)") (class "Default")
      (node (ref "D16") (pin "C") (pinfunction "C_C") (pintype "passive"))
      (node (ref "D17") (pin "A") (pinfunction "A_A") (pintype "passive"))
    )
    (net (code "19") (name "Net-(D17-PadC)") (class "Default")
      (node (ref "D17") (pin "C") (pinfunction "C_C") (pintype "passive"))
      (node (ref "R5") (pin "1") (pinfunction "1_1") (pintype "passive"))
    )
    (net (code "20") (name "Net-(D18-PadC)") (class "Default")
      (node (ref "D18") (pin "C") (pinfunction "C_C") (pintype "passive"))
      (node (ref "D19") (pin "A") (pinfunction "A_A") (pintype "passive"))
    )
    (net (code "21") (name "Net-(D19-PadC)") (class "Default")
      (node (ref "D19") (pin "C") (pinfunction "C_C") (pintype "passive"))
      (node (ref "D20") (pin "A") (pinfunction "A_A") (pintype "passive"))
    )
    (net (code "22") (name "Net-(D20-PadC)") (class "Default")
      (node (ref "D20") (pin "C") (pinfunction "C_C") (pintype "passive"))
      (node (ref "D21") (pin "A") (pinfunction "A_A") (pintype "passive"))
    )
    (net (code "23") (name "Net-(D21-PadC)") (class "Default")
      (node (ref "D21") (pin "C") (pinfunction "C_C") (pintype "passive"))
      (node (ref "D22") (pin "A") (pinfunction "A_A") (pintype "passive"))
    )
    (net (code "24") (name "Net-(D22-PadC)") (class "Default")
      (node (ref "D22") (pin "C") (pinfunction "C_C") (pintype "passive"))
      (node (ref "R6") (pin "1") (pinfunction "1_1") (pintype "passive"))
    )
    (net (code "25") (name "Net-(D23-PadC)") (class "Default")
      (node (ref "D23") (pin "C") (pinfunction "C_C") (pintype "passive"))
      (node (ref "D24") (pin "A") (pinfunction "A_A") (pintype "passive"))
    )
    (net (code "26") (name "Net-(D24-PadC)") (class "Default")
      (node (ref "D24") (pin "C") (pinfunction "C_C") (pintype "passive"))
      (node (ref "D25") (pin "A") (pinfunction "A_A") (pintype "passive"))
    )
    (net (code "27") (name "Net-(D25-PadC)") (class "Default")
      (node (ref "D25") (pin "C") (pinfunction "C_C") (pintype "passive"))
      (node (ref "D26") (pin "A") (pinfunction "A_A") (pintype "passive"))
    )
    (net (code "28") (name "Net-(D26-PadC)") (class "Default")
      (node (ref "D26") (pin "C") (pinfunction "C_C") (pintype "passive"))
      (node (ref "D27") (pin "A") (pinfunction "A_A") (pintype "passive"))
    )
    (net (code "29") (name "Net-(D27-PadC)") (class "Default")
      (node (ref "D27") (pin "C") (pinfunction "C_C") (pintype "passive"))
      (node (ref "R7") (pin "1") (pinfunction "1_1") (pintype "passive"))
    )
    (net (code "30") (name "Net-(D28-PadC)") (class "Default")
      (node (ref "D28") (pin "C") (pinfunction "C_C") (pintype "passive"))
      (node (ref "D29") (pin "A") (pinfunction "A_A") (pintype "passive"))
    )
    (net (code "31") (name "Net-(D29-PadC)") (class "Default")
      (node (ref "D29") (pin "C") (pinfunction "C_C") (pintype "passive"))
      (node (ref "D30") (pin "A") (pinfunction "A_A") (pintype "passive"))
    )
    (net (code "32") (name "Net-(D30-PadC)") (class "Default")
      (node (ref "D30") (pin "C") (pinfunction "C_C") (pintype "passive"))
      (node (ref "R8") (pin "1") (pinfunction "1_1") (pintype "passive"))
    )
    (net (code "33") (name "Net-(D31-PadC)") (class "Default")
      (node (ref "D31") (pin "C") (pinfunction "C_C") (pintype "passive"))
      (node (ref "D32") (pin "A") (pinfunction "A_A") (pintype "passive"))
    )
    (net (code "34") (name "Net-(D32-PadC)") (class "Default")
      (node (ref "D32") (pin "C") (pinfunction "C_C") (pintype "passive"))
      (node (ref "D33") (pin "A") (pinfunction "A_A") (pintype "passive"))
    )
    (net (code "35") (name "Net-(D33-PadC)") (class "Default")
      (node (ref "D33") (pin "C") (pinfunction "C_C") (pintype "passive"))
      (node (ref "R9") (pin "1") (pinfunction "1_1") (pintype "passive"))
    )
    (net (code "36") (name "Net-(D34-PadC)") (class "Default")
      (node (ref "D34") (pin "C") (pinfunction "C_C") (pintype "passive"))
      (node (ref "D35") (pin "A") (pinfunction "A_A") (pintype "passive"))
    )
    (net (code "37") (name "Net-(D35-PadC)") (class "Default")
      (node (ref "D35") (pin "C") (pinfunction "C_C") (pintype "passive"))
      (node (ref "D36") (pin "A") (pinfunction "A_A") (pintype "passive"))
    )
    (net (code "38") (name "Net-(D36-PadC)") (class "Default")
      (node (ref "D36") (pin "C") (pinfunction "C_C") (pintype "passive"))
      (node (ref "D37") (pin "A") (pinfunction "A_A") (pintype "passive"))
    )
    (net (code "39") (name "Net-(D37-PadC)") (class "Default")
      (node (ref "D37") (pin "C") (pinfunction "C_C") (pintype "passive"))
      (node (ref "D38") (pin "A") (pinfunction "A_A") (pintype "passive"))
    )
    (net (code "40") (name "Net-(D38-PadC)") (class "Default")
      (node (ref "D38") (pin "C") (pinfunction "C_C") (pintype "passive"))
      (node (ref "R10") (pin "1") (pinfunction "1_1") (pintype "passive"))
    )
    (net (code "41") (name "Net-(D39-PadC)") (class "Default")
      (node (ref "D39") (pin "C") (pinfunction "C_C") (pintype "passive"))
      (node (ref "D40") (pin "A") (pinfunction "A_A") (pintype "passive"))
    )
    (net (code "42") (name "Net-(D40-PadC)") (class "Default")
      (node (ref "D40") (pin "C") (pinfunction "C_C") (pintype "passive"))
      (node (ref "D41") (pin "A") (pinfunction "A_A") (pintype "passive"))
    )
    (net (code "43") (name "Net-(D41-PadC)") (class "Default")
      (node (ref "D41") (pin "C") (pinfunction "C_C") (pintype "passive"))
      (node (ref "R11") (pin "1") (pinfunction "1_1") (pintype "passive"))
    )
    (net (code "44") (name "Net-(D42-PadC)") (class "Default")
      (node (ref "D42") (pin "C") (pinfunction "C_C") (pintype "passive"))
      (node (ref "D43") (pin "A") (pinfunction "A_A") (pintype "passive"))
    )
    (net (code "45") (name "Net-(D43-PadC)") (class "Default")
      (node (ref "D43") (pin "C") (pinfunction "C_C") (pintype "passive"))
      (node (ref "D44") (pin "A") (pinfunction "A_A") (pintype "passive"))
    )
    (net (code "46") (name "Net-(D44-PadC)") (class "Default")
      (node (ref "D44") (pin "C") (pinfunction "C_C") (pintype "passive"))
      (node (ref "R12") (pin "1") (pinfunction "1_1") (pintype "passive"))
    )
    (net (code "47") (name "Net-(D45-PadC)") (class "Default")
      (node (ref "D45") (pin "C") (pinfunction "C_C") (pintype "passive"))
      (node (ref "D46") (pin "A") (pinfunction "A_A") (pintype "passive"))
    )
    (net (code "48") (name "Net-(D46-PadC)") (class "Default")
      (node (ref "D46") (pin "C") (pinfunction "C_C") (pintype "passive"))
      (node (ref "D47") (pin "A") (pinfunction "A_A") (pintype "passive"))
    )
    (net (code "49") (name "Net-(D47-PadC)") (class "Default")
      (node (ref "D47") (pin "C") (pinfunction "C_C") (pintype "passive"))
      (node (ref "R13") (pin "1") (pinfunction "1_1") (pintype "passive"))
    )
    (net (code "50") (name "Net-(D48-PadC)") (class "Default")
      (node (ref "D48") (pin "C") (pinfunction "C_C") (pintype "passive"))
      (node (ref "D49") (pin "A") (pinfunction "A_A") (pintype "passive"))
    )
    (net (code "51") (name "Net-(D49-PadC)") (class "Default")
      (node (ref "D49") (pin "C") (pinfunction "C_C") (pintype "passive"))
      (node (ref "D50") (pin "A") (pinfunction "A_A") (pintype "passive"))
    )
    (net (code "52") (name "Net-(D50-PadC)") (class "Default")
      (node (ref "D50") (pin "C") (pinfunction "C_C") (pintype "passive"))
      (node (ref "R14") (pin "1") (pinfunction "1_1") (pintype "passive"))
    )
    (net (code "53") (name "Net-(D51-PadC)") (class "Default")
      (node (ref "D51") (pin "C") (pinfunction "C_C") (pintype "passive"))
      (node (ref "D52") (pin "A") (pinfunction "A_A") (pintype "passive"))
    )
    (net (code "54") (name "Net-(D52-PadC)") (class "Default")
      (node (ref "D52") (pin "C") (pinfunction "C_C") (pintype "passive"))
      (node (ref "D53") (pin "A") (pinfunction "A_A") (pintype "passive"))
    )
    (net (code "55") (name "Net-(D53-PadC)") (class "Default")
      (node (ref "D53") (pin "C") (pinfunction "C_C") (pintype "passive"))
      (node (ref "D54") (pin "A") (pinfunction "A_A") (pintype "passive"))
    )
    (net (code "56") (name "Net-(D54-PadC)") (class "Default")
      (node (ref "D54") (pin "C") (pinfunction "C_C") (pintype "passive"))
      (node (ref "D55") (pin "A") (pinfunction "A_A") (pintype "passive"))
    )
    (net (code "57") (name "Net-(D55-PadC)") (class "Default")
      (node (ref "D55") (pin "C") (pinfunction "C_C") (pintype "passive"))
      (node (ref "R15") (pin "1") (pinfunction "1_1") (pintype "passive"))
    )
    (net (code "58") (name "Net-(D56-PadC)") (class "Default")
      (node (ref "D56") (pin "C") (pinfunction "C_C") (pintype "passive"))
      (node (ref "D57") (pin "A") (pinfunction "A_A") (pintype "passive"))
    )
    (net (code "59") (name "Net-(D57-PadC)") (class "Default")
      (node (ref "D57") (pin "C") (pinfunction "C_C") (pintype "passive"))
      (node (ref "D58") (pin "A") (pinfunction "A_A") (pintype "passive"))
    )
    (net (code "60") (name "Net-(D58-PadC)") (class "Default")
      (node (ref "D58") (pin "C") (pinfunction "C_C") (pintype "passive"))
      (node (ref "R16") (pin "1") (pinfunction "1_1") (pintype "passive"))
    )
    (net (code "61") (name "Net-(D59-PadC)") (class "Default")
      (node (ref "D59") (pin "C") (pinfunction "C_C") (pintype "passive"))
      (node (ref "D60") (pin "A") (pinfunction "A_A") (pintype "passive"))
    )
    (net (code "62") (name "Net-(D60-PadC)") (class "Default")
      (node (ref "D60") (pin "C") (pinfunction "C_C") (pintype "passive"))
      (node (ref "D61") (pin "A") (pinfunction "A_A") (pintype "passive"))
    )
    (net (code "63") (name "Net-(D61-PadC)") (class "Default")
      (node (ref "D61") (pin "C") (pinfunction "C_C") (pintype "passive"))
      (node (ref "R17") (pin "1") (pinfunction "1_1") (pintype "passive"))
    )
    (net (code "64") (name "Net-(D62-PadC)") (class "Default")
      (node (ref "D62") (pin "C") (pinfunction "C_C") (pintype "passive"))
      (node (ref "D63") (pin "A") (pinfunction "A_A") (pintype "passive"))
    )
    (net (code "65") (name "Net-(D63-PadC)") (class "Default")
      (node (ref "D63") (pin "C") (pinfunction "C_C") (pintype "passive"))
      (node (ref "D64") (pin "A") (pinfunction "A_A") (pintype "passive"))
    )
    (net (code "66") (name "Net-(D64-PadC)") (class "Default")
      (node (ref "D64") (pin "C") (pinfunction "C_C") (pintype "passive"))
      (node (ref "R18") (pin "1") (pinfunction "1_1") (pintype "passive"))
    )
    (net (code "67") (name "Net-(D65-PadC)") (class "Default")
      (node (ref "D65") (pin "C") (pinfunction "C_C") (pintype "passive"))
      (node (ref "D66") (pin "A") (pinfunction "A_A") (pintype "passive"))
    )
    (net (code "68") (name "Net-(D66-PadC)") (class "Default")
      (node (ref "D66") (pin "C") (pinfunction "C_C") (pintype "passive"))
      (node (ref "D67") (pin "A") (pinfunction "A_A") (pintype "passive"))
    )
    (net (code "69") (name "Net-(D67-PadC)") (class "Default")
      (node (ref "D67") (pin "C") (pinfunction "C_C") (pintype "passive"))
      (node (ref "R19") (pin "1") (pinfunction "1_1") (pintype "passive"))
    )
    (net (code "70") (name "Net-(D68-PadC)") (class "Default")
      (node (ref "D68") (pin "C") (pinfunction "C_C") (pintype "passive"))
      (node (ref "D69") (pin "A") (pinfunction "A_A") (pintype "passive"))
    )
    (net (code "71") (name "Net-(D69-PadC)") (class "Default")
      (node (ref "D69") (pin "C") (pinfunction "C_C") (pintype "passive"))
      (node (ref "D70") (pin "A") (pinfunction "A_A") (pintype "passive"))
    )
    (net (code "72") (name "Net-(D70-PadC)") (class "Default")
      (node (ref "D70") (pin "C") (pinfunction "C_C") (pintype "passive"))
      (node (ref "R20") (pin "1") (pinfunction "1_1") (pintype "passive"))
    )
    (net (code "73") (name "Net-(D71-PadC)") (class "Default")
      (node (ref "D71") (pin "C") (pinfunction "C_C") (pintype "passive"))
      (node (ref "D72") (pin "A") (pinfunction "A_A") (pintype "passive"))
    )
    (net (code "74") (name "Net-(D72-PadC)") (class "Default")
      (node (ref "D72") (pin "C") (pinfunction "C_C") (pintype "passive"))
      (node (ref "D73") (pin "A") (pinfunction "A_A") (pintype "passive"))
    )
    (net (code "75") (name "Net-(D73-PadC)") (class "Default")
      (node (ref "D73") (pin "C") (pinfunction "C_C") (pintype "passive"))
      (node (ref "R21") (pin "1") (pinfunction "1_1") (pintype "passive"))
    )
    (net (code "76") (name "Net-(D74-PadC)") (class "Default")
      (node (ref "D74") (pin "C") (pinfunction "C_C") (pintype "passive"))
      (node (ref "D75") (pin "A") (pinfunction "A_A") (pintype "passive"))
    )
    (net (code "77") (name "Net-(D75-PadC)") (class "Default")
      (node (ref "D75") (pin "C") (pinfunction "C_C") (pintype "passive"))
      (node (ref "D76") (pin "A") (pinfunction "A_A") (pintype "passive"))
    )
    (net (code "78") (name "Net-(D76-PadC)") (class "Default")
      (node (ref "D76") (pin "C") (pinfunction "C_C") (pintype "passive"))
      (node (ref "R22") (pin "1") (pinfunction "1_1") (pintype "passive"))
    )
    (net (code "79") (name "Net-(D77-PadC)") (class "Default")
      (node (ref "D77") (pin "C") (pinfunction "C_C") (pintype "passive"))
      (node (ref "D78") (pin "A") (pinfunction "A_A") (pintype "passive"))
    )
    (net (code "80") (name "Net-(D78-PadC)") (class "Default")
      (node (ref "D78") (pin "C") (pinfunction "C_C") (pintype "passive"))
      (node (ref "D79") (pin "A") (pinfunction "A_A") (pintype "passive"))
    )
    (net (code "81") (name "Net-(D79-PadC)") (class "Default")
      (node (ref "D79") (pin "C") (pinfunction "C_C") (pintype "passive"))
      (node (ref "R23") (pin "1") (pinfunction "1_1") (pintype "passive"))
    )
    (net (code "82") (name "Net-(D80-PadC)") (class "Default")
      (node (ref "D80") (pin "C") (pinfunction "C_C") (pintype "passive"))
      (node (ref "D81") (pin "A") (pinfunction "A_A") (pintype "passive"))
    )
    (net (code "83") (name "Net-(D81-PadC)") (class "Default")
      (node (ref "D81") (pin "C") (pinfunction "C_C") (pintype "passive"))
      (node (ref "D82") (pin "A") (pinfunction "A_A") (pintype "passive"))
    )
    (net (code "84") (name "Net-(D82-PadC)") (class "Default")
      (node (ref "D82") (pin "C") (pinfunction "C_C") (pintype "passive"))
      (node (ref "R24") (pin "1") (pinfunction "1_1") (pintype "passive"))
    )
    (net (code "85") (name "Net-(D83-PadC)") (class "Default")
      (node (ref "D83") (pin "C") (pinfunction "C_C") (pintype "passive"))
      (node (ref "D84") (pin "A") (pinfunction "A_A") (pintype "passive"))
    )
    (net (code "86") (name "Net-(D84-PadC)") (class "Default")
      (node (ref "D84") (pin "C") (pinfunction "C_C") (pintype "passive"))
      (node (ref "D85") (pin "A") (pinfunction "A_A") (pintype "passive"))
    )
    (net (code "87") (name "Net-(D85-PadC)") (class "Default")
      (node (ref "D85") (pin "C") (pinfunction "C_C") (pintype "passive"))
      (node (ref "R25") (pin "1") (pinfunction "1_1") (pintype "passive"))
    )
    (net (code "88") (name "Net-(D86-PadC)") (class "Default")
      (node (ref "D86") (pin "C") (pinfunction "C_C") (pintype "passive"))
      (node (ref "D87") (pin "A") (pinfunction "A_A") (pintype "passive"))
    )
    (net (code "89") (name "Net-(D87-PadC)") (class "Default")
      (node (ref "D87") (pin "C") (pinfunction "C_C") (pintype "passive"))
      (node (ref "D88") (pin "A") (pinfunction "A_A") (pintype "passive"))
    )
    (net (code "90") (name "Net-(D88-PadC)") (class "Default")
      (node (ref "D88") (pin "C") (pinfunction "C_C") (pintype "passive"))
      (node (ref "D89") (pin "A") (pinfunction "A_A") (pintype "passive"))
    )
    (net (code "91") (name "Net-(D89-PadC)") (class "Default")
      (node (ref "D89") (pin "C") (pinfunction "C_C") (pintype "passive"))
      (node (ref "D90") (pin "A") (pinfunction "A_A") (pintype "passive"))
    )
    (net (code "92") (name "Net-(D90-PadC)") (class "Default")
      (node (ref "D90") (pin "C") (pinfunction "C_C") (pintype "passive"))
      (node (ref "R26") (pin "1") (pinfunction "1_1") (pintype "passive"))
    )
    (net (code "93") (name "SECOND_GND") (class "Default")
      (node (ref "P2") (pin "GND") (pinfunction "2_GND") (pintype "passive"))
      (node (ref "P5") (pin "GND") (pinfunction "2_GND") (pintype "passive"))
      (node (ref "R12") (pin "2") (pinfunction "2_2") (pintype "passive"))
      (node (ref "R14") (pin "2") (pinfunction "2_2") (pintype "passive"))
      (node (ref "R17") (pin "2") (pinfunction "2_2") (pintype "passive"))
      (node (ref "R19") (pin "2") (pinfunction "2_2") (pintype "passive"))
      (node (ref "R2") (pin "2") (pinfunction "2_2") (pintype "passive"))
      (node (ref "R21") (pin "2") (pinfunction "2_2") (pintype "passive"))
      (node (ref "R23") (pin "2") (pinfunction "2_2") (pintype "passive"))
      (node (ref "R25") (pin "2") (pinfunction "2_2") (pintype "passive"))
      (node (ref "R5") (pin "2") (pinfunction "2_2") (pintype "passive"))
      (node (ref "R9") (pin "2") (pinfunction "2_2") (pintype "passive"))
    )
    (net (code "94") (name "SECOND_VCC") (class "Default")
      (node (ref "D15") (pin "A") (pinfunction "A_A") (pintype "passive"))
      (node (ref "D31") (pin "A") (pinfunction "A_A") (pintype "passive"))
      (node (ref "D4") (pin "A") (pinfunction "A_A") (pintype "passive"))
      (node (ref "D42") (pin "A") (pinfunction "A_A") (pintype "passive"))
      (node (ref "D48") (pin "A") (pinfunction "A_A") (pintype "passive"))
      (node (ref "D59") (pin "A") (pinfunction "A_A") (pintype "passive"))
      (node (ref "D65") (pin "A") (pinfunction "A_A") (pintype "passive"))
      (node (ref "D71") (pin "A") (pinfunction "A_A") (pintype "passive"))
      (node (ref "D77") (pin "A") (pinfunction "A_A") (pintype "passive"))
      (node (ref "D83") (pin "A") (pinfunction "A_A") (pintype "passive"))
      (node (ref "P2") (pin "VCC") (pinfunction "1_VCC") (pintype "passive"))
      (node (ref "P5") (pin "VCC") (pinfunction "1_VCC") (pintype "passive"))
    )
    (net (code "95") (name "THIRD_GND") (class "Default")
      (node (ref "P3") (pin "GND") (pinfunction "2_GND") (pintype "passive"))
      (node (ref "P6") (pin "GND") (pinfunction "2_GND") (pintype "passive"))
      (node (ref "R10") (pin "2") (pinfunction "2_2") (pintype "passive"))
      (node (ref "R15") (pin "2") (pinfunction "2_2") (pintype "passive"))
      (node (ref "R26") (pin "2") (pinfunction "2_2") (pintype "passive"))
      (node (ref "R3") (pin "2") (pinfunction "2_2") (pintype "passive"))
      (node (ref "R6") (pin "2") (pinfunction "2_2") (pintype "passive"))
      (node (ref "R7") (pin "2") (pinfunction "2_2") (pintype "passive"))
    )
    (net (code "96") (name "THIRD_VCC") (class "Default")
      (node (ref "D18") (pin "A") (pinfunction "A_A") (pintype "passive"))
      (node (ref "D23") (pin "A") (pinfunction "A_A") (pintype "passive"))
      (node (ref "D34") (pin "A") (pinfunction "A_A") (pintype "passive"))
      (node (ref "D51") (pin "A") (pinfunction "A_A") (pintype "passive"))
      (node (ref "D7") (pin "A") (pinfunction "A_A") (pintype "passive"))
      (node (ref "D86") (pin "A") (pinfunction "A_A") (pintype "passive"))
      (node (ref "P3") (pin "VCC") (pinfunction "1_VCC") (pintype "passive"))
      (node (ref "P6") (pin "VCC") (pinfunction "1_VCC") (pintype "passive"))
    )
  )
)
